# DimmerRGB_RevA.net
KiCad netlist of a schematic drawn in EAGLE
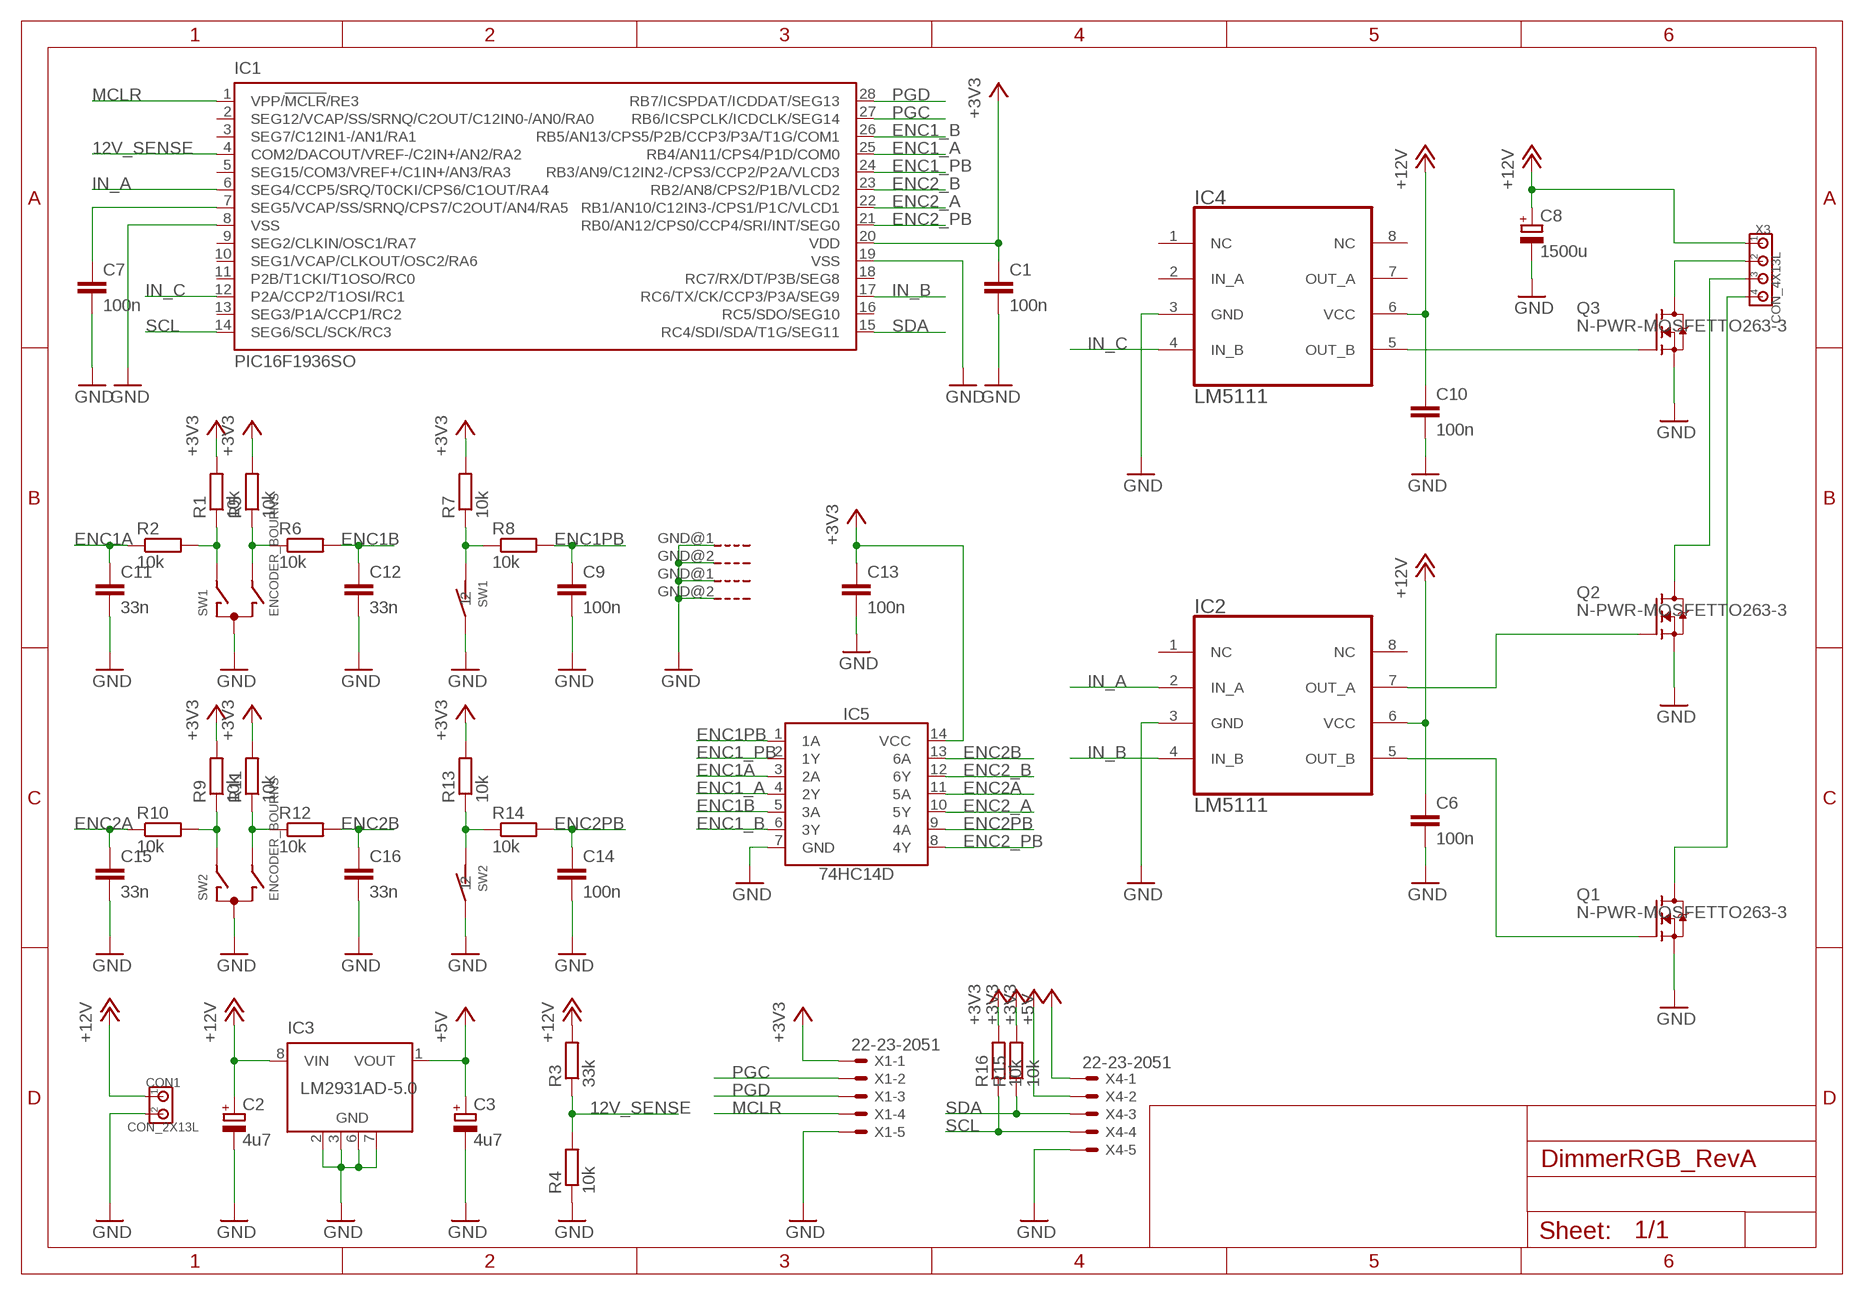
[diagram p0: schematic, sheet 1]

(export (version "E")
  (design (tool "Eeschema 10.0.6"))
  (components
    (comp (ref "C1")
      (value "100n")
      (footprint "eagle-import:C0805")
      (libsource (lib "eagle-import") (part "CC0805"))
    )
    (comp (ref "C2")
      (value "4u7")
      (footprint "eagle-import:SMC_C")
      (libsource (lib "eagle-import") (part "C_POLARIZEDSMC_C"))
    )
    (comp (ref "C3")
      (value "4u7")
      (footprint "eagle-import:SMC_C")
      (libsource (lib "eagle-import") (part "C_POLARIZEDSMC_C"))
    )
    (comp (ref "C6")
      (value "100n")
      (footprint "eagle-import:C0805")
      (libsource (lib "eagle-import") (part "CC0805"))
    )
    (comp (ref "C7")
      (value "100n")
      (footprint "eagle-import:C0805")
      (libsource (lib "eagle-import") (part "CC0805"))
    )
    (comp (ref "C8")
      (value "1500u")
      (footprint "eagle-import:10MM")
      (libsource (lib "eagle-import") (part "C_POLARIZED10MM"))
    )
    (comp (ref "C9")
      (value "100n")
      (footprint "eagle-import:C0805")
      (libsource (lib "eagle-import") (part "CC0805"))
    )
    (comp (ref "C10")
      (value "100n")
      (footprint "eagle-import:C0805")
      (libsource (lib "eagle-import") (part "CC0805"))
    )
    (comp (ref "C11")
      (value "33n")
      (footprint "eagle-import:C0805")
      (libsource (lib "eagle-import") (part "CC0805"))
    )
    (comp (ref "C12")
      (value "33n")
      (footprint "eagle-import:C0805")
      (libsource (lib "eagle-import") (part "CC0805"))
    )
    (comp (ref "C13")
      (value "100n")
      (footprint "eagle-import:C0805")
      (libsource (lib "eagle-import") (part "CC0805"))
    )
    (comp (ref "C14")
      (value "100n")
      (footprint "eagle-import:C0805")
      (libsource (lib "eagle-import") (part "CC0805"))
    )
    (comp (ref "C15")
      (value "33n")
      (footprint "eagle-import:C0805")
      (libsource (lib "eagle-import") (part "CC0805"))
    )
    (comp (ref "C16")
      (value "33n")
      (footprint "eagle-import:C0805")
      (libsource (lib "eagle-import") (part "CC0805"))
    )
    (comp (ref "CON1")
      (value "CON_2X13L")
      (footprint "eagle-import:200MIL_2X")
      (libsource (lib "eagle-import") (part "CON_2X13L"))
    )
    (comp (ref "IC1")
      (value "PIC16F1936SO")
      (footprint "eagle-import:SO28W")
      (libsource (lib "eagle-import") (part "PIC16F19SO36"))
    )
    (comp (ref "IC2")
      (value "LM5111")
      (footprint "eagle-import:SOIC8")
      (libsource (lib "eagle-import") (part "LM5111"))
    )
    (comp (ref "IC3")
      (value "LM2931AD-5.0")
      (footprint "eagle-import:SO8")
      (libsource (lib "eagle-import") (part "LM2931AD-5.0"))
    )
    (comp (ref "IC4")
      (value "LM5111")
      (footprint "eagle-import:SOIC8")
      (libsource (lib "eagle-import") (part "LM5111"))
    )
    (comp (ref "IC5")
      (value "74HC14D")
      (footprint "eagle-import:SO14")
      (libsource (lib "eagle-import") (part "74HC14D"))
    )
    (comp (ref "Q1")
      (value "N-PWR-MOSFETTO263-3")
      (footprint "eagle-import:TO263-3")
      (libsource (lib "eagle-import") (part "N-PWR-MOSFETTO263-3"))
    )
    (comp (ref "Q2")
      (value "N-PWR-MOSFETTO263-3")
      (footprint "eagle-import:TO263-3")
      (libsource (lib "eagle-import") (part "N-PWR-MOSFETTO263-3"))
    )
    (comp (ref "Q3")
      (value "N-PWR-MOSFETTO263-3")
      (footprint "eagle-import:TO263-3")
      (libsource (lib "eagle-import") (part "N-PWR-MOSFETTO263-3"))
    )
    (comp (ref "R1")
      (value "10k")
      (footprint "eagle-import:R0805")
      (libsource (lib "eagle-import") (part "RESISTORR0805"))
    )
    (comp (ref "R2")
      (value "10k")
      (footprint "eagle-import:R0805")
      (libsource (lib "eagle-import") (part "RESISTORR0805"))
    )
    (comp (ref "R3")
      (value "33k")
      (footprint "eagle-import:R0805")
      (libsource (lib "eagle-import") (part "RESISTORR0805"))
    )
    (comp (ref "R4")
      (value "10k")
      (footprint "eagle-import:R0805")
      (libsource (lib "eagle-import") (part "RESISTORR0805"))
    )
    (comp (ref "R5")
      (value "10k")
      (footprint "eagle-import:R0805")
      (libsource (lib "eagle-import") (part "RESISTORR0805"))
    )
    (comp (ref "R6")
      (value "10k")
      (footprint "eagle-import:R0805")
      (libsource (lib "eagle-import") (part "RESISTORR0805"))
    )
    (comp (ref "R7")
      (value "10k")
      (footprint "eagle-import:R0805")
      (libsource (lib "eagle-import") (part "RESISTORR0805"))
    )
    (comp (ref "R8")
      (value "10k")
      (footprint "eagle-import:R0805")
      (libsource (lib "eagle-import") (part "RESISTORR0805"))
    )
    (comp (ref "R9")
      (value "10k")
      (footprint "eagle-import:R0805")
      (libsource (lib "eagle-import") (part "RESISTORR0805"))
    )
    (comp (ref "R10")
      (value "10k")
      (footprint "eagle-import:R0805")
      (libsource (lib "eagle-import") (part "RESISTORR0805"))
    )
    (comp (ref "R11")
      (value "10k")
      (footprint "eagle-import:R0805")
      (libsource (lib "eagle-import") (part "RESISTORR0805"))
    )
    (comp (ref "R12")
      (value "10k")
      (footprint "eagle-import:R0805")
      (libsource (lib "eagle-import") (part "RESISTORR0805"))
    )
    (comp (ref "R13")
      (value "10k")
      (footprint "eagle-import:R0805")
      (libsource (lib "eagle-import") (part "RESISTORR0805"))
    )
    (comp (ref "R14")
      (value "10k")
      (footprint "eagle-import:R0805")
      (libsource (lib "eagle-import") (part "RESISTORR0805"))
    )
    (comp (ref "R15")
      (value "10k")
      (footprint "eagle-import:R0805")
      (libsource (lib "eagle-import") (part "RESISTORR0805"))
    )
    (comp (ref "R16")
      (value "10k")
      (footprint "eagle-import:R0805")
      (libsource (lib "eagle-import") (part "RESISTORR0805"))
    )
    (comp (ref "SW1")
      (value "ENCODER_BOURNS")
      (footprint "eagle-import:ENCODER_BOURNS")
      (libsource (lib "eagle-import") (part "ENCODER_BOURNS"))
    )
    (comp (ref "SW2")
      (value "ENCODER_BOURNS")
      (footprint "eagle-import:ENCODER_BOURNS")
      (libsource (lib "eagle-import") (part "ENCODER_BOURNS"))
    )
    (comp (ref "X1")
      (value "22-23-2051")
      (footprint "eagle-import:22-23-2051")
      (fields (field (name "MF") "MOLEX"))
      (libsource (lib "eagle-import") (part "22-23-2051"))
    )
    (comp (ref "X3")
      (value "CON_4X13L")
      (footprint "eagle-import:200MIL_4X")
      (libsource (lib "eagle-import") (part "CON_4X13L"))
    )
    (comp (ref "X4")
      (value "22-23-2051")
      (footprint "eagle-import:22-23-2051")
      (fields (field (name "MF") "MOLEX"))
      (libsource (lib "eagle-import") (part "22-23-2051"))
    )
  )
  (nets
    (net (code "1") (name "+3V3") (class "Default")
      (node (ref "C1") (pin "1") (pinfunction "1_1") (pintype "passive"))
      (node (ref "C13") (pin "1") (pinfunction "1_1") (pintype "passive"))
      (node (ref "IC1") (pin "20") (pinfunction "VDD_20") (pintype "power_in"))
      (node (ref "IC5") (pin "14") (pinfunction "VCC_14") (pintype "power_in"))
      (node (ref "R1") (pin "2") (pinfunction "2_2") (pintype "passive"))
      (node (ref "R11") (pin "2") (pinfunction "2_2") (pintype "passive"))
      (node (ref "R13") (pin "2") (pinfunction "2_2") (pintype "passive"))
      (node (ref "R15") (pin "2") (pinfunction "2_2") (pintype "passive"))
      (node (ref "R16") (pin "2") (pinfunction "2_2") (pintype "passive"))
      (node (ref "R5") (pin "2") (pinfunction "2_2") (pintype "passive"))
      (node (ref "R7") (pin "2") (pinfunction "2_2") (pintype "passive"))
      (node (ref "R9") (pin "2") (pinfunction "2_2") (pintype "passive"))
      (node (ref "X1") (pin "1") (pinfunction "S_1") (pintype "passive"))
      (node (ref "X4") (pin "2") (pinfunction "S_2") (pintype "passive"))
    )
    (net (code "2") (name "+5V") (class "Default")
      (node (ref "C3") (pin "+") (pinfunction "+_+") (pintype "passive"))
      (node (ref "IC3") (pin "1") (pinfunction "VOUT_1") (pintype "output"))
      (node (ref "X4") (pin "1") (pinfunction "S_1") (pintype "passive"))
    )
    (net (code "3") (name "+12V") (class "Default")
      (node (ref "C10") (pin "1") (pinfunction "1_1") (pintype "passive"))
      (node (ref "C2") (pin "+") (pinfunction "+_+") (pintype "passive"))
      (node (ref "C6") (pin "1") (pinfunction "1_1") (pintype "passive"))
      (node (ref "C8") (pin "+") (pinfunction "+_+") (pintype "passive"))
      (node (ref "CON1") (pin "1") (pinfunction "1_1") (pintype "passive"))
      (node (ref "IC2") (pin "6") (pinfunction "VCC_6") (pintype "input"))
      (node (ref "IC3") (pin "8") (pinfunction "VIN_8") (pintype "passive"))
      (node (ref "IC4") (pin "6") (pinfunction "VCC_6") (pintype "input"))
      (node (ref "R3") (pin "2") (pinfunction "2_2") (pintype "passive"))
      (node (ref "X3") (pin "1") (pinfunction "1_1") (pintype "passive"))
    )
    (net (code "4") (name "/12V_SENSE") (class "Default")
      (node (ref "IC1") (pin "4") (pinfunction "COM2/DACOUT/VREF-/C2IN+/AN2/RA2_4") (pintype "bidirectional"))
      (node (ref "R3") (pin "1") (pinfunction "1_1") (pintype "passive"))
      (node (ref "R4") (pin "2") (pinfunction "2_2") (pintype "passive"))
    )
    (net (code "5") (name "/ENC1A") (class "Default")
      (node (ref "C11") (pin "1") (pinfunction "1_1") (pintype "passive"))
      (node (ref "IC5") (pin "3") (pinfunction "2A_3") (pintype "input"))
      (node (ref "R2") (pin "1") (pinfunction "1_1") (pintype "passive"))
    )
    (net (code "6") (name "/ENC1B") (class "Default")
      (node (ref "C12") (pin "1") (pinfunction "1_1") (pintype "passive"))
      (node (ref "IC5") (pin "5") (pinfunction "3A_5") (pintype "input"))
      (node (ref "R6") (pin "2") (pinfunction "2_2") (pintype "passive"))
    )
    (net (code "7") (name "/ENC1PB") (class "Default")
      (node (ref "C9") (pin "1") (pinfunction "1_1") (pintype "passive"))
      (node (ref "IC5") (pin "1") (pinfunction "1A_1") (pintype "input"))
      (node (ref "R8") (pin "2") (pinfunction "2_2") (pintype "passive"))
    )
    (net (code "8") (name "/ENC1_A") (class "Default")
      (node (ref "IC1") (pin "25") (pinfunction "RB4/AN11/CPS4/P1D/COM0_25") (pintype "bidirectional"))
      (node (ref "IC5") (pin "4") (pinfunction "2Y_4") (pintype "input"))
    )
    (net (code "9") (name "/ENC1_B") (class "Default")
      (node (ref "IC1") (pin "26") (pinfunction "RB5/AN13/CPS5/P2B/CCP3/P3A/T1G/COM1_26") (pintype "bidirectional"))
      (node (ref "IC5") (pin "6") (pinfunction "3Y_6") (pintype "input"))
    )
    (net (code "10") (name "/ENC1_PB") (class "Default")
      (node (ref "IC1") (pin "24") (pinfunction "RB3/AN9/C12IN2-/CPS3/CCP2/P2A/VLCD3_24") (pintype "bidirectional"))
      (node (ref "IC5") (pin "2") (pinfunction "1Y_2") (pintype "input"))
    )
    (net (code "11") (name "/ENC2A") (class "Default")
      (node (ref "C15") (pin "1") (pinfunction "1_1") (pintype "passive"))
      (node (ref "IC5") (pin "11") (pinfunction "5A_11") (pintype "bidirectional"))
      (node (ref "R10") (pin "1") (pinfunction "1_1") (pintype "passive"))
    )
    (net (code "12") (name "/ENC2B") (class "Default")
      (node (ref "C16") (pin "1") (pinfunction "1_1") (pintype "passive"))
      (node (ref "IC5") (pin "13") (pinfunction "6A_13") (pintype "bidirectional"))
      (node (ref "R12") (pin "2") (pinfunction "2_2") (pintype "passive"))
    )
    (net (code "13") (name "/ENC2PB") (class "Default")
      (node (ref "C14") (pin "1") (pinfunction "1_1") (pintype "passive"))
      (node (ref "IC5") (pin "9") (pinfunction "4A_9") (pintype "bidirectional"))
      (node (ref "R14") (pin "2") (pinfunction "2_2") (pintype "passive"))
    )
    (net (code "14") (name "/ENC2_A") (class "Default")
      (node (ref "IC1") (pin "22") (pinfunction "RB1/AN10/C12IN3-/CPS1/P1C/VLCD1_22") (pintype "bidirectional"))
      (node (ref "IC5") (pin "10") (pinfunction "5Y_10") (pintype "bidirectional"))
    )
    (net (code "15") (name "/ENC2_B") (class "Default")
      (node (ref "IC1") (pin "23") (pinfunction "RB2/AN8/CPS2/P1B/VLCD2_23") (pintype "bidirectional"))
      (node (ref "IC5") (pin "12") (pinfunction "6Y_12") (pintype "bidirectional"))
    )
    (net (code "16") (name "/ENC2_PB") (class "Default")
      (node (ref "IC1") (pin "21") (pinfunction "RB0/AN12/CPS0/CCP4/SRI/INT/SEG0_21") (pintype "bidirectional"))
      (node (ref "IC5") (pin "8") (pinfunction "4Y_8") (pintype "bidirectional"))
    )
    (net (code "17") (name "/IN_A") (class "Default")
      (node (ref "IC1") (pin "6") (pinfunction "SEG4/CCP5/SRQ/T0CKI/CPS6/C1OUT/RA4_6") (pintype "bidirectional"))
      (node (ref "IC2") (pin "2") (pinfunction "IN_A_2") (pintype "input"))
    )
    (net (code "18") (name "/IN_B") (class "Default")
      (node (ref "IC1") (pin "17") (pinfunction "RC6/TX/CK/CCP3/P3A/SEG9_17") (pintype "bidirectional"))
      (node (ref "IC2") (pin "4") (pinfunction "IN_B_4") (pintype "passive"))
    )
    (net (code "19") (name "/IN_C") (class "Default")
      (node (ref "IC1") (pin "12") (pinfunction "P2A/CCP2/T1OSI/RC1_12") (pintype "bidirectional"))
      (node (ref "IC4") (pin "4") (pinfunction "IN_B_4") (pintype "passive"))
    )
    (net (code "20") (name "/MCLR") (class "Default")
      (node (ref "IC1") (pin "1") (pinfunction "VPP/~{MCLR}/RE3_1") (pintype "input"))
      (node (ref "X1") (pin "4") (pinfunction "S_4") (pintype "passive"))
    )
    (net (code "21") (name "/PGC") (class "Default")
      (node (ref "IC1") (pin "27") (pinfunction "RB6/ICSPCLK/ICDCLK/SEG14_27") (pintype "bidirectional"))
      (node (ref "X1") (pin "2") (pinfunction "S_2") (pintype "passive"))
    )
    (net (code "22") (name "/PGD") (class "Default")
      (node (ref "IC1") (pin "28") (pinfunction "RB7/ICSPDAT/ICDDAT/SEG13_28") (pintype "bidirectional"))
      (node (ref "X1") (pin "3") (pinfunction "S_3") (pintype "passive"))
    )
    (net (code "23") (name "/SCL") (class "Default")
      (node (ref "IC1") (pin "14") (pinfunction "SEG6/SCL/SCK/RC3_14") (pintype "bidirectional"))
      (node (ref "R16") (pin "1") (pinfunction "1_1") (pintype "passive"))
      (node (ref "X4") (pin "4") (pinfunction "S_4") (pintype "passive"))
    )
    (net (code "24") (name "/SDA") (class "Default")
      (node (ref "IC1") (pin "15") (pinfunction "RC4/SDI/SDA/T1G/SEG11_15") (pintype "bidirectional"))
      (node (ref "R15") (pin "1") (pinfunction "1_1") (pintype "passive"))
      (node (ref "X4") (pin "3") (pinfunction "S_3") (pintype "passive"))
    )
    (net (code "25") (name "GND") (class "Default")
      (node (ref "C1") (pin "2") (pinfunction "2_2") (pintype "passive"))
      (node (ref "C10") (pin "2") (pinfunction "2_2") (pintype "passive"))
      (node (ref "C11") (pin "2") (pinfunction "2_2") (pintype "passive"))
      (node (ref "C12") (pin "2") (pinfunction "2_2") (pintype "passive"))
      (node (ref "C13") (pin "2") (pinfunction "2_2") (pintype "passive"))
      (node (ref "C14") (pin "2") (pinfunction "2_2") (pintype "passive"))
      (node (ref "C15") (pin "2") (pinfunction "2_2") (pintype "passive"))
      (node (ref "C16") (pin "2") (pinfunction "2_2") (pintype "passive"))
      (node (ref "C2") (pin "-") (pinfunction "-_-") (pintype "passive"))
      (node (ref "C3") (pin "-") (pinfunction "-_-") (pintype "passive"))
      (node (ref "C6") (pin "2") (pinfunction "2_2") (pintype "passive"))
      (node (ref "C7") (pin "2") (pinfunction "2_2") (pintype "passive"))
      (node (ref "C8") (pin "-") (pinfunction "-_-") (pintype "passive"))
      (node (ref "C9") (pin "2") (pinfunction "2_2") (pintype "passive"))
      (node (ref "CON1") (pin "2") (pinfunction "2_2") (pintype "passive"))
      (node (ref "IC1") (pin "19") (pinfunction "VSS_19") (pintype "power_in"))
      (node (ref "IC1") (pin "8") (pinfunction "VSS_8") (pintype "power_in"))
      (node (ref "IC2") (pin "3") (pinfunction "GND_3") (pintype "input"))
      (node (ref "IC3") (pin "2") (pinfunction "GND_2") (pintype "power_in"))
      (node (ref "IC3") (pin "3") (pinfunction "GND_3") (pintype "power_in"))
      (node (ref "IC3") (pin "6") (pinfunction "GND_6") (pintype "power_in"))
      (node (ref "IC3") (pin "7") (pinfunction "GND_7") (pintype "power_in"))
      (node (ref "IC4") (pin "3") (pinfunction "GND_3") (pintype "input"))
      (node (ref "IC5") (pin "7") (pinfunction "GND_7") (pintype "bidirectional"))
      (node (ref "Q1") (pin "3") (pinfunction "S_3") (pintype "passive"))
      (node (ref "Q2") (pin "3") (pinfunction "S_3") (pintype "passive"))
      (node (ref "Q3") (pin "3") (pinfunction "S_3") (pintype "passive"))
      (node (ref "R4") (pin "1") (pinfunction "1_1") (pintype "passive"))
      (node (ref "SW1") (pin "2") (pinfunction "2_2") (pintype "passive"))
      (node (ref "SW1") (pin "C") (pinfunction "C_C") (pintype "passive"))
      (node (ref "SW1") (pin "GND@1") (pinfunction "G_GND@1") (pintype "passive"))
      (node (ref "SW1") (pin "GND@2") (pinfunction "G_GND@2") (pintype "passive"))
      (node (ref "SW2") (pin "2") (pinfunction "2_2") (pintype "passive"))
      (node (ref "SW2") (pin "C") (pinfunction "C_C") (pintype "passive"))
      (node (ref "SW2") (pin "GND@1") (pinfunction "G_GND@1") (pintype "passive"))
      (node (ref "SW2") (pin "GND@2") (pinfunction "G_GND@2") (pintype "passive"))
      (node (ref "X1") (pin "5") (pinfunction "S_5") (pintype "passive"))
      (node (ref "X4") (pin "5") (pinfunction "S_5") (pintype "passive"))
    )
    (net (code "26") (name "Net-(IC1-SEG5{slash}VCAP{slash}SS{slash}SRNQ{slash}CPS7{slash}C2OUT{slash}AN4{slash}RA5)") (class "Default")
      (node (ref "C7") (pin "1") (pinfunction "1_1") (pintype "passive"))
      (node (ref "IC1") (pin "7") (pinfunction "SEG5/VCAP/SS/SRNQ/CPS7/C2OUT/AN4/RA5_7") (pintype "bidirectional"))
    )
    (net (code "27") (name "Net-(IC2-OUT_A)") (class "Default")
      (node (ref "IC2") (pin "7") (pinfunction "OUT_A_7") (pintype "input"))
      (node (ref "Q2") (pin "1") (pinfunction "G_1") (pintype "passive"))
    )
    (net (code "28") (name "Net-(IC2-OUT_B)") (class "Default")
      (node (ref "IC2") (pin "5") (pinfunction "OUT_B_5") (pintype "bidirectional"))
      (node (ref "Q1") (pin "1") (pinfunction "G_1") (pintype "passive"))
    )
    (net (code "29") (name "Net-(IC4-OUT_B)") (class "Default")
      (node (ref "IC4") (pin "5") (pinfunction "OUT_B_5") (pintype "bidirectional"))
      (node (ref "Q3") (pin "1") (pinfunction "G_1") (pintype "passive"))
    )
    (net (code "30") (name "Net-(Q1-D)") (class "Default")
      (node (ref "Q1") (pin "TAB") (pinfunction "D_TAB") (pintype "passive"))
      (node (ref "X3") (pin "4") (pinfunction "4_4") (pintype "passive"))
    )
    (net (code "31") (name "Net-(Q2-D)") (class "Default")
      (node (ref "Q2") (pin "TAB") (pinfunction "D_TAB") (pintype "passive"))
      (node (ref "X3") (pin "3") (pinfunction "3_3") (pintype "passive"))
    )
    (net (code "32") (name "Net-(Q3-D)") (class "Default")
      (node (ref "Q3") (pin "TAB") (pinfunction "D_TAB") (pintype "passive"))
      (node (ref "X3") (pin "2") (pinfunction "2_2") (pintype "passive"))
    )
    (net (code "33") (name "Net-(R1-Pad1)") (class "Default")
      (node (ref "R1") (pin "1") (pinfunction "1_1") (pintype "passive"))
      (node (ref "R2") (pin "2") (pinfunction "2_2") (pintype "passive"))
      (node (ref "SW1") (pin "A") (pinfunction "A_A") (pintype "passive"))
    )
    (net (code "34") (name "Net-(R5-Pad1)") (class "Default")
      (node (ref "R5") (pin "1") (pinfunction "1_1") (pintype "passive"))
      (node (ref "R6") (pin "1") (pinfunction "1_1") (pintype "passive"))
      (node (ref "SW1") (pin "B") (pinfunction "B_B") (pintype "passive"))
    )
    (net (code "35") (name "Net-(R7-Pad1)") (class "Default")
      (node (ref "R7") (pin "1") (pinfunction "1_1") (pintype "passive"))
      (node (ref "R8") (pin "1") (pinfunction "1_1") (pintype "passive"))
      (node (ref "SW1") (pin "1") (pinfunction "1_1") (pintype "passive"))
    )
    (net (code "36") (name "Net-(R10-Pad2)") (class "Default")
      (node (ref "R10") (pin "2") (pinfunction "2_2") (pintype "passive"))
      (node (ref "R9") (pin "1") (pinfunction "1_1") (pintype "passive"))
      (node (ref "SW2") (pin "A") (pinfunction "A_A") (pintype "passive"))
    )
    (net (code "37") (name "Net-(R11-Pad1)") (class "Default")
      (node (ref "R11") (pin "1") (pinfunction "1_1") (pintype "passive"))
      (node (ref "R12") (pin "1") (pinfunction "1_1") (pintype "passive"))
      (node (ref "SW2") (pin "B") (pinfunction "B_B") (pintype "passive"))
    )
    (net (code "38") (name "Net-(R13-Pad1)") (class "Default")
      (node (ref "R13") (pin "1") (pinfunction "1_1") (pintype "passive"))
      (node (ref "R14") (pin "1") (pinfunction "1_1") (pintype "passive"))
      (node (ref "SW2") (pin "1") (pinfunction "1_1") (pintype "passive"))
    )
    (net (code "39") (name "unconnected-(IC1-P2B{slash}T1CKI{slash}T1OSO{slash}RC0-Pad11)") (class "Default")
      (node (ref "IC1") (pin "11") (pinfunction "P2B/T1CKI/T1OSO/RC0_11") (pintype "bidirectional"))
    )
    (net (code "40") (name "unconnected-(IC1-RC5{slash}SDO{slash}SEG10-Pad16)") (class "Default")
      (node (ref "IC1") (pin "16") (pinfunction "RC5/SDO/SEG10_16") (pintype "bidirectional"))
    )
    (net (code "41") (name "unconnected-(IC1-RC7{slash}RX{slash}DT{slash}P3B{slash}SEG8-Pad18)") (class "Default")
      (node (ref "IC1") (pin "18") (pinfunction "RC7/RX/DT/P3B/SEG8_18") (pintype "bidirectional"))
    )
    (net (code "42") (name "unconnected-(IC1-SEG1{slash}VCAP{slash}CLKOUT{slash}OSC2{slash}RA6-Pad10)") (class "Default")
      (node (ref "IC1") (pin "10") (pinfunction "SEG1/VCAP/CLKOUT/OSC2/RA6_10") (pintype "bidirectional"))
    )
    (net (code "43") (name "unconnected-(IC1-SEG2{slash}CLKIN{slash}OSC1{slash}RA7-Pad9)") (class "Default")
      (node (ref "IC1") (pin "9") (pinfunction "SEG2/CLKIN/OSC1/RA7_9") (pintype "bidirectional"))
    )
    (net (code "44") (name "unconnected-(IC1-SEG3{slash}P1A{slash}CCP1{slash}RC2-Pad13)") (class "Default")
      (node (ref "IC1") (pin "13") (pinfunction "SEG3/P1A/CCP1/RC2_13") (pintype "bidirectional"))
    )
    (net (code "45") (name "unconnected-(IC1-SEG7{slash}C12IN1-{slash}AN1{slash}RA1-Pad3)") (class "Default")
      (node (ref "IC1") (pin "3") (pinfunction "SEG7/C12IN1-/AN1/RA1_3") (pintype "bidirectional"))
    )
    (net (code "46") (name "unconnected-(IC1-SEG12{slash}VCAP{slash}SS{slash}SRNQ{slash}C2OUT{slash}C12IN0-{slash}AN0{slash}RA0-Pad2)") (class "Default")
      (node (ref "IC1") (pin "2") (pinfunction "SEG12/VCAP/SS/SRNQ/C2OUT/C12IN0-/AN0/RA0_2") (pintype "bidirectional"))
    )
    (net (code "47") (name "unconnected-(IC1-SEG15{slash}COM3{slash}VREF+{slash}C1IN+{slash}AN3{slash}RA3-Pad5)") (class "Default")
      (node (ref "IC1") (pin "5") (pinfunction "SEG15/COM3/VREF+/C1IN+/AN3/RA3_5") (pintype "bidirectional"))
    )
    (net (code "48") (name "unconnected-(IC2-NC-Pad1)") (class "Default")
      (node (ref "IC2") (pin "1") (pinfunction "NC_1") (pintype "no_connect"))
    )
    (net (code "49") (name "unconnected-(IC2-NC-Pad8)") (class "Default")
      (node (ref "IC2") (pin "8") (pinfunction "NC_8") (pintype "no_connect"))
    )
    (net (code "50") (name "unconnected-(IC4-IN_A-Pad2)") (class "Default")
      (node (ref "IC4") (pin "2") (pinfunction "IN_A_2") (pintype "input"))
    )
    (net (code "51") (name "unconnected-(IC4-NC-Pad1)") (class "Default")
      (node (ref "IC4") (pin "1") (pinfunction "NC_1") (pintype "no_connect"))
    )
    (net (code "52") (name "unconnected-(IC4-NC-Pad8)") (class "Default")
      (node (ref "IC4") (pin "8") (pinfunction "NC_8") (pintype "no_connect"))
    )
    (net (code "53") (name "unconnected-(IC4-OUT_A-Pad7)") (class "Default")
      (node (ref "IC4") (pin "7") (pinfunction "OUT_A_7") (pintype "input"))
    )
  )
)
